# EC_Feather_Breakout_3_2.net
KiCad netlist of a schematic drawn in EAGLE
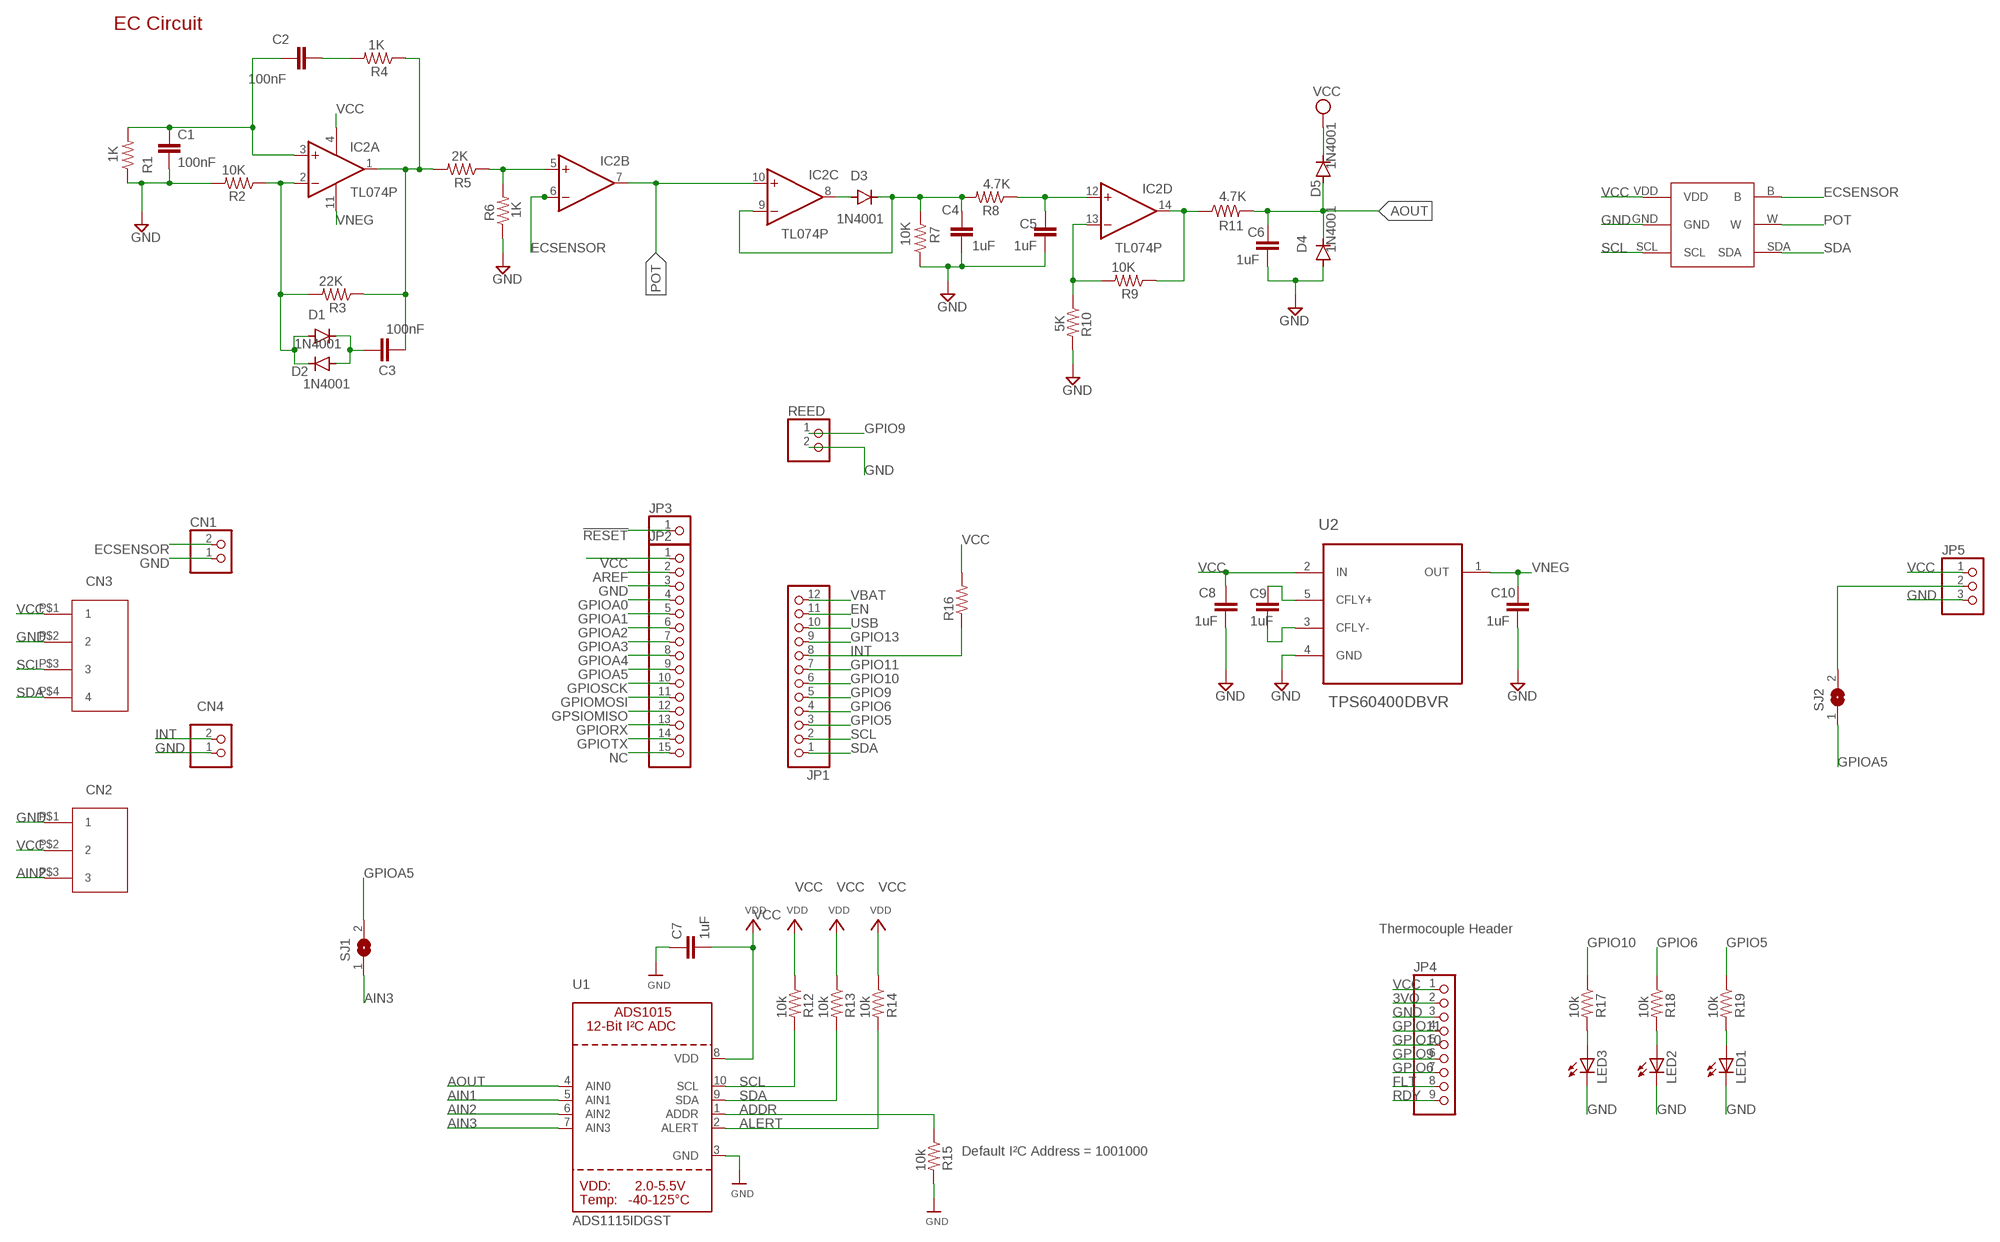
[diagram p0: schematic, sheet 1]

(export (version "E")
  (design (tool "Eeschema 10.0.6"))
  (components
    (comp (ref "C1")
      (value "100nF")
      (footprint "eagle-import:C1206")
      (libsource (lib "eagle-import") (part "C-EUC1206"))
    )
    (comp (ref "C2")
      (value "100nF")
      (footprint "eagle-import:C1206")
      (libsource (lib "eagle-import") (part "C-EUC1206"))
    )
    (comp (ref "C3")
      (value "100nF")
      (footprint "eagle-import:C1206")
      (libsource (lib "eagle-import") (part "C-EUC1206"))
    )
    (comp (ref "C4")
      (value "1uF")
      (footprint "eagle-import:C1206")
      (libsource (lib "eagle-import") (part "C-EUC1206"))
    )
    (comp (ref "C5")
      (value "1uF")
      (footprint "eagle-import:C1206")
      (libsource (lib "eagle-import") (part "C-EUC1206"))
    )
    (comp (ref "C6")
      (value "1uF")
      (footprint "eagle-import:C1206")
      (libsource (lib "eagle-import") (part "C-EUC1206"))
    )
    (comp (ref "C7")
      (value "1uF")
      (footprint "eagle-import:C1206")
      (libsource (lib "eagle-import") (part "C-EUC1206"))
    )
    (comp (ref "C8")
      (value "1uF")
      (footprint "eagle-import:C1206")
      (libsource (lib "eagle-import") (part "C-EUC1206"))
    )
    (comp (ref "C9")
      (value "1uF")
      (footprint "eagle-import:C1206")
      (libsource (lib "eagle-import") (part "C-EUC1206"))
    )
    (comp (ref "C10")
      (value "1uF")
      (footprint "eagle-import:C1206")
      (libsource (lib "eagle-import") (part "C-EUC1206"))
    )
    (comp (ref "CN1")
      (value "JST_2PIN-THM")
      (footprint "eagle-import:JST-PH-2-THM")
      (libsource (lib "eagle-import") (part "JST_2PIN-THM"))
    )
    (comp (ref "CN4")
      (value "JST_2PIN-THM")
      (footprint "eagle-import:JST-PH-2-THM")
      (libsource (lib "eagle-import") (part "JST_2PIN-THM"))
    )
    (comp (ref "D1")
      (value "1N4001")
      (footprint "eagle-import:D-5")
      (libsource (lib "eagle-import") (part "DIODE-D-5"))
    )
    (comp (ref "D2")
      (value "1N4001")
      (footprint "eagle-import:D-5")
      (libsource (lib "eagle-import") (part "DIODE-D-5"))
    )
    (comp (ref "D3")
      (value "1N4001")
      (footprint "eagle-import:D-5")
      (libsource (lib "eagle-import") (part "DIODE-D-5"))
    )
    (comp (ref "D4")
      (value "1N4001")
      (footprint "eagle-import:D-5")
      (libsource (lib "eagle-import") (part "DIODE-D-5"))
    )
    (comp (ref "D5")
      (value "1N4001")
      (footprint "eagle-import:D-5")
      (libsource (lib "eagle-import") (part "DIODE-D-5"))
    )
    (comp (ref "IC2")
      (value "TL074P")
      (footprint "eagle-import:DIL14")
      (libsource (lib "eagle-import") (part "TL074P"))
    )
    (comp (ref "JP1")
      (value "PINHD-1X12-CB")
      (footprint "eagle-import:1X12-CB")
      (libsource (lib "eagle-import") (part "PINHD-1X12-CB"))
    )
    (comp (ref "JP2")
      (value "PINHD-1X15-CB")
      (footprint "eagle-import:1X15-CB")
      (libsource (lib "eagle-import") (part "PINHD-1X15-CB"))
    )
    (comp (ref "JP3")
      (value "PINHD-1X1CB")
      (footprint "eagle-import:1X01-CLEANBIG")
      (libsource (lib "eagle-import") (part "PINHD-1X1CB"))
    )
    (comp (ref "JP4")
      (value "PINHD-1X9")
      (footprint "eagle-import:1X09")
      (libsource (lib "eagle-import") (part "PINHD-1X9"))
    )
    (comp (ref "JP5")
      (value "PINHD-1X3CB")
      (footprint "eagle-import:1X03-CLEANBIG")
      (libsource (lib "eagle-import") (part "PINHD-1X3CB"))
    )
    (comp (ref "LED1")
      (value "LEDSMT1206")
      (footprint "eagle-import:1206")
      (libsource (lib "eagle-import") (part "LEDSMT1206"))
    )
    (comp (ref "LED2")
      (value "LEDSMT1206")
      (footprint "eagle-import:1206")
      (libsource (lib "eagle-import") (part "LEDSMT1206"))
    )
    (comp (ref "LED3")
      (value "LEDSMT1206")
      (footprint "eagle-import:1206")
      (libsource (lib "eagle-import") (part "LEDSMT1206"))
    )
    (comp (ref "R1")
      (value "1K")
      (footprint "eagle-import:R1206")
      (libsource (lib "eagle-import") (part "rcl_334_R-US_R1206"))
    )
    (comp (ref "R2")
      (value "10K")
      (footprint "eagle-import:R1206")
      (libsource (lib "eagle-import") (part "rcl_334_R-US_R1206"))
    )
    (comp (ref "R3")
      (value "22K")
      (footprint "eagle-import:R1206")
      (libsource (lib "eagle-import") (part "rcl_334_R-US_R1206"))
    )
    (comp (ref "R4")
      (value "1K")
      (footprint "eagle-import:R1206")
      (libsource (lib "eagle-import") (part "rcl_334_R-US_R1206"))
    )
    (comp (ref "R5")
      (value "2K")
      (footprint "eagle-import:R1206")
      (libsource (lib "eagle-import") (part "rcl_334_R-US_R1206"))
    )
    (comp (ref "R6")
      (value "1K")
      (footprint "eagle-import:R1206")
      (libsource (lib "eagle-import") (part "rcl_334_R-US_R1206"))
    )
    (comp (ref "R7")
      (value "10K")
      (footprint "eagle-import:R1206")
      (libsource (lib "eagle-import") (part "rcl_334_R-US_R1206"))
    )
    (comp (ref "R8")
      (value "4.7K")
      (footprint "eagle-import:R1206")
      (libsource (lib "eagle-import") (part "rcl_334_R-US_R1206"))
    )
    (comp (ref "R9")
      (value "10K")
      (footprint "eagle-import:R1206")
      (libsource (lib "eagle-import") (part "rcl_334_R-US_R1206"))
    )
    (comp (ref "R10")
      (value "5K")
      (footprint "eagle-import:R1206")
      (libsource (lib "eagle-import") (part "rcl_334_R-US_R1206"))
    )
    (comp (ref "R11")
      (value "4.7K")
      (footprint "eagle-import:R1206")
      (libsource (lib "eagle-import") (part "rcl_334_R-US_R1206"))
    )
    (comp (ref "R12")
      (value "10k")
      (footprint "eagle-import:R1206")
      (libsource (lib "eagle-import") (part "rcl_334_R-US_R1206"))
    )
    (comp (ref "R13")
      (value "10k")
      (footprint "eagle-import:R1206")
      (libsource (lib "eagle-import") (part "rcl_334_R-US_R1206"))
    )
    (comp (ref "R14")
      (value "10k")
      (footprint "eagle-import:R1206")
      (libsource (lib "eagle-import") (part "rcl_334_R-US_R1206"))
    )
    (comp (ref "R15")
      (value "10k")
      (footprint "eagle-import:R1206")
      (libsource (lib "eagle-import") (part "rcl_334_R-US_R1206"))
    )
    (comp (ref "R16")
      (value "R-US_M1206")
      (footprint "eagle-import:M1206")
      (libsource (lib "eagle-import") (part "R-US_M1206"))
    )
    (comp (ref "R17")
      (value "10k")
      (footprint "eagle-import:R1206")
      (libsource (lib "eagle-import") (part "rcl_334_R-US_R1206"))
    )
    (comp (ref "R18")
      (value "10k")
      (footprint "eagle-import:R1206")
      (libsource (lib "eagle-import") (part "rcl_334_R-US_R1206"))
    )
    (comp (ref "R19")
      (value "10k")
      (footprint "eagle-import:R1206")
      (libsource (lib "eagle-import") (part "rcl_334_R-US_R1206"))
    )
    (comp (ref "REED")
      (value "PINHD-1X2")
      (footprint "eagle-import:1X02")
      (libsource (lib "eagle-import") (part "PINHD-1X2"))
    )
    (comp (ref "SJ1") (value "SJ") (footprint "eagle-import:SJ") (libsource (lib "eagle-import") (part "SJ")))
    (comp (ref "SJ2") (value "SJ") (footprint "eagle-import:SJ") (libsource (lib "eagle-import") (part "SJ")))
    (comp (ref "U$1")
      (value "AD5246")
      (footprint "eagle-import:AD5246")
      (libsource (lib "eagle-import") (part "AD5246"))
    )
    (comp (ref "U$7")
      (value "JST_4PIN_2MM")
      (footprint "eagle-import:JST_4PIN_2MM")
      (libsource (lib "eagle-import") (part "JST_4PIN_2MM"))
    )
    (comp (ref "U$9")
      (value "JST_3PIN_2MM")
      (footprint "eagle-import:JST_3PIN_2MM")
      (libsource (lib "eagle-import") (part "JST_3PIN_2MM"))
    )
    (comp (ref "U1")
      (value "ADS1115IDGST")
      (footprint "eagle-import:MSOP10")
      (libsource (lib "eagle-import") (part "ADC_ADS1015"))
    )
    (comp (ref "U2")
      (value "TPS60400DBVR")
      (footprint "eagle-import:SOT95P280X145-5N")
      (fields (field (name "MF") "Texas Instruments"))
      (libsource (lib "eagle-import") (part "TPS60400DBVR"))
    )
  )
  (nets
    (net (code "1") (name "/3VO") (class "Default")
      (node (ref "JP4") (pin "2") (pinfunction "2_2") (pintype "passive"))
    )
    (net (code "2") (name "/ADDR") (class "Default")
      (node (ref "R15") (pin "1") (pinfunction "1_1") (pintype "passive"))
      (node (ref "U1") (pin "1") (pinfunction "ADDR_1") (pintype "bidirectional"))
    )
    (net (code "3") (name "/AIN1") (class "Default")
      (node (ref "U1") (pin "5") (pinfunction "AIN1_5") (pintype "bidirectional"))
    )
    (net (code "4") (name "/AIN2") (class "Default")
      (node (ref "U$9") (pin "P$3") (pinfunction "3_P$3") (pintype "bidirectional"))
      (node (ref "U1") (pin "6") (pinfunction "AIN2_6") (pintype "bidirectional"))
    )
    (net (code "5") (name "/AIN3") (class "Default")
      (node (ref "SJ1") (pin "1") (pinfunction "1_1") (pintype "passive"))
      (node (ref "U1") (pin "7") (pinfunction "AIN3_7") (pintype "bidirectional"))
    )
    (net (code "6") (name "/ALERT") (class "Default")
      (node (ref "R14") (pin "2") (pinfunction "2_2") (pintype "passive"))
      (node (ref "U1") (pin "2") (pinfunction "ALERT_2") (pintype "bidirectional"))
    )
    (net (code "7") (name "/AREF") (class "Default")
      (node (ref "JP2") (pin "2") (pinfunction "2_2") (pintype "passive"))
    )
    (net (code "8") (name "/ECSENSOR") (class "Default")
      (node (ref "CN1") (pin "2") (pinfunction "1_2") (pintype "passive"))
      (node (ref "IC2") (pin "6") (pinfunction "-IN_6") (pintype "input"))
      (node (ref "U$1") (pin "B") (pinfunction "B_B") (pintype "bidirectional"))
    )
    (net (code "9") (name "/EN") (class "Default")
      (node (ref "JP1") (pin "11") (pinfunction "11_11") (pintype "passive"))
    )
    (net (code "10") (name "/FLT") (class "Default")
      (node (ref "JP4") (pin "8") (pinfunction "8_8") (pintype "passive"))
    )
    (net (code "11") (name "/GPIO5") (class "Default")
      (node (ref "JP1") (pin "3") (pinfunction "3_3") (pintype "passive"))
      (node (ref "R19") (pin "1") (pinfunction "1_1") (pintype "passive"))
    )
    (net (code "12") (name "/GPIO6") (class "Default")
      (node (ref "JP1") (pin "4") (pinfunction "4_4") (pintype "passive"))
      (node (ref "JP4") (pin "7") (pinfunction "7_7") (pintype "passive"))
      (node (ref "R18") (pin "1") (pinfunction "1_1") (pintype "passive"))
    )
    (net (code "13") (name "/GPIO9") (class "Default")
      (node (ref "JP1") (pin "5") (pinfunction "5_5") (pintype "passive"))
      (node (ref "JP4") (pin "6") (pinfunction "6_6") (pintype "passive"))
      (node (ref "REED") (pin "1") (pinfunction "1_1") (pintype "passive"))
    )
    (net (code "14") (name "/GPIO10") (class "Default")
      (node (ref "JP1") (pin "6") (pinfunction "6_6") (pintype "passive"))
      (node (ref "JP4") (pin "5") (pinfunction "5_5") (pintype "passive"))
      (node (ref "R17") (pin "1") (pinfunction "1_1") (pintype "passive"))
    )
    (net (code "15") (name "/GPIO11") (class "Default")
      (node (ref "JP1") (pin "7") (pinfunction "7_7") (pintype "passive"))
      (node (ref "JP4") (pin "4") (pinfunction "4_4") (pintype "passive"))
    )
    (net (code "16") (name "/GPIO13") (class "Default")
      (node (ref "JP1") (pin "9") (pinfunction "9_9") (pintype "passive"))
    )
    (net (code "17") (name "/GPIOA0") (class "Default")
      (node (ref "JP2") (pin "4") (pinfunction "4_4") (pintype "passive"))
    )
    (net (code "18") (name "/GPIOA1") (class "Default")
      (node (ref "JP2") (pin "5") (pinfunction "5_5") (pintype "passive"))
    )
    (net (code "19") (name "/GPIOA2") (class "Default")
      (node (ref "JP2") (pin "6") (pinfunction "6_6") (pintype "passive"))
    )
    (net (code "20") (name "/GPIOA3") (class "Default")
      (node (ref "JP2") (pin "7") (pinfunction "7_7") (pintype "passive"))
    )
    (net (code "21") (name "/GPIOA4") (class "Default")
      (node (ref "JP2") (pin "8") (pinfunction "8_8") (pintype "passive"))
    )
    (net (code "22") (name "/GPIOA5") (class "Default")
      (node (ref "JP2") (pin "9") (pinfunction "9_9") (pintype "passive"))
      (node (ref "SJ1") (pin "2") (pinfunction "2_2") (pintype "passive"))
      (node (ref "SJ2") (pin "1") (pinfunction "1_1") (pintype "passive"))
    )
    (net (code "23") (name "/GPIOMOSI") (class "Default")
      (node (ref "JP2") (pin "11") (pinfunction "11_11") (pintype "passive"))
    )
    (net (code "24") (name "/GPIORX") (class "Default")
      (node (ref "JP2") (pin "13") (pinfunction "13_13") (pintype "passive"))
    )
    (net (code "25") (name "/GPIOSCK") (class "Default")
      (node (ref "JP2") (pin "10") (pinfunction "10_10") (pintype "passive"))
    )
    (net (code "26") (name "/GPIOTX") (class "Default")
      (node (ref "JP2") (pin "14") (pinfunction "14_14") (pintype "passive"))
    )
    (net (code "27") (name "/GPSIOMISO") (class "Default")
      (node (ref "JP2") (pin "12") (pinfunction "12_12") (pintype "passive"))
    )
    (net (code "28") (name "/INT") (class "Default")
      (node (ref "CN4") (pin "2") (pinfunction "1_2") (pintype "passive"))
      (node (ref "JP1") (pin "8") (pinfunction "8_8") (pintype "passive"))
      (node (ref "R16") (pin "1") (pinfunction "1_1") (pintype "passive"))
    )
    (net (code "29") (name "/NC") (class "Default")
      (node (ref "JP2") (pin "15") (pinfunction "15_15") (pintype "passive"))
    )
    (net (code "30") (name "/RDY") (class "Default")
      (node (ref "JP4") (pin "9") (pinfunction "9_9") (pintype "passive"))
    )
    (net (code "31") (name "/SCL") (class "Default")
      (node (ref "JP1") (pin "2") (pinfunction "2_2") (pintype "passive"))
      (node (ref "R12") (pin "2") (pinfunction "2_2") (pintype "passive"))
      (node (ref "U$1") (pin "SCL") (pinfunction "SCL_SCL") (pintype "bidirectional"))
      (node (ref "U$7") (pin "P$3") (pinfunction "3_P$3") (pintype "bidirectional"))
      (node (ref "U1") (pin "10") (pinfunction "SCL_10") (pintype "bidirectional"))
    )
    (net (code "32") (name "/SDA") (class "Default")
      (node (ref "JP1") (pin "1") (pinfunction "1_1") (pintype "passive"))
      (node (ref "R13") (pin "2") (pinfunction "2_2") (pintype "passive"))
      (node (ref "U$1") (pin "SDA") (pinfunction "SDA_SDA") (pintype "bidirectional"))
      (node (ref "U$7") (pin "P$4") (pinfunction "4_P$4") (pintype "bidirectional"))
      (node (ref "U1") (pin "9") (pinfunction "SDA_9") (pintype "bidirectional"))
    )
    (net (code "33") (name "/USB") (class "Default")
      (node (ref "JP1") (pin "10") (pinfunction "10_10") (pintype "passive"))
    )
    (net (code "34") (name "/VBAT") (class "Default")
      (node (ref "JP1") (pin "12") (pinfunction "12_12") (pintype "passive"))
    )
    (net (code "35") (name "/VNEG") (class "Default")
      (node (ref "C10") (pin "2") (pinfunction "2_2") (pintype "passive"))
      (node (ref "IC2") (pin "11") (pinfunction "V-_11") (pintype "power_in"))
      (node (ref "U2") (pin "1") (pinfunction "OUT_1") (pintype "output"))
    )
    (net (code "36") (name "/~{RESET}") (class "Default")
      (node (ref "JP3") (pin "1") (pinfunction "1_1") (pintype "passive"))
    )
    (net (code "37") (name "AOUT") (class "Default")
      (node (ref "C6") (pin "2") (pinfunction "2_2") (pintype "passive"))
      (node (ref "D4") (pin "C") (pinfunction "C_C") (pintype "passive"))
      (node (ref "D5") (pin "A") (pinfunction "A_A") (pintype "passive"))
      (node (ref "R11") (pin "2") (pinfunction "2_2") (pintype "passive"))
      (node (ref "U1") (pin "4") (pinfunction "AIN0_4") (pintype "bidirectional"))
    )
    (net (code "38") (name "GND") (class "Default")
      (node (ref "C1") (pin "2") (pinfunction "2_2") (pintype "passive"))
      (node (ref "C10") (pin "1") (pinfunction "1_1") (pintype "passive"))
      (node (ref "C4") (pin "1") (pinfunction "1_1") (pintype "passive"))
      (node (ref "C5") (pin "1") (pinfunction "1_1") (pintype "passive"))
      (node (ref "C6") (pin "1") (pinfunction "1_1") (pintype "passive"))
      (node (ref "C7") (pin "1") (pinfunction "1_1") (pintype "passive"))
      (node (ref "C8") (pin "1") (pinfunction "1_1") (pintype "passive"))
      (node (ref "CN1") (pin "1") (pinfunction "2_1") (pintype "passive"))
      (node (ref "CN4") (pin "1") (pinfunction "2_1") (pintype "passive"))
      (node (ref "D4") (pin "A") (pinfunction "A_A") (pintype "passive"))
      (node (ref "JP2") (pin "3") (pinfunction "3_3") (pintype "passive"))
      (node (ref "JP4") (pin "3") (pinfunction "3_3") (pintype "passive"))
      (node (ref "JP5") (pin "3") (pinfunction "3_3") (pintype "passive"))
      (node (ref "LED1") (pin "C") (pinfunction "C_C") (pintype "passive"))
      (node (ref "LED2") (pin "C") (pinfunction "C_C") (pintype "passive"))
      (node (ref "LED3") (pin "C") (pinfunction "C_C") (pintype "passive"))
      (node (ref "R1") (pin "1") (pinfunction "1_1") (pintype "passive"))
      (node (ref "R10") (pin "2") (pinfunction "2_2") (pintype "passive"))
      (node (ref "R15") (pin "2") (pinfunction "2_2") (pintype "passive"))
      (node (ref "R2") (pin "2") (pinfunction "2_2") (pintype "passive"))
      (node (ref "R6") (pin "1") (pinfunction "1_1") (pintype "passive"))
      (node (ref "R7") (pin "1") (pinfunction "1_1") (pintype "passive"))
      (node (ref "REED") (pin "2") (pinfunction "2_2") (pintype "passive"))
      (node (ref "U$1") (pin "GND") (pinfunction "GND_GND") (pintype "bidirectional"))
      (node (ref "U$7") (pin "P$2") (pinfunction "2_P$2") (pintype "bidirectional"))
      (node (ref "U$9") (pin "P$1") (pinfunction "1_P$1") (pintype "bidirectional"))
      (node (ref "U1") (pin "3") (pinfunction "GND_3") (pintype "bidirectional"))
      (node (ref "U2") (pin "4") (pinfunction "GND_4") (pintype "passive"))
    )
    (net (code "39") (name "Net-(C2-Pad2)") (class "Default")
      (node (ref "C2") (pin "2") (pinfunction "2_2") (pintype "passive"))
      (node (ref "R4") (pin "2") (pinfunction "2_2") (pintype "passive"))
    )
    (net (code "40") (name "Net-(C3-Pad1)") (class "Default")
      (node (ref "C3") (pin "1") (pinfunction "1_1") (pintype "passive"))
      (node (ref "D1") (pin "C") (pinfunction "C_C") (pintype "passive"))
      (node (ref "D2") (pin "A") (pinfunction "A_A") (pintype "passive"))
    )
    (net (code "41") (name "Net-(IC2A-+IN)") (class "Default")
      (node (ref "C1") (pin "1") (pinfunction "1_1") (pintype "passive"))
      (node (ref "C2") (pin "1") (pinfunction "1_1") (pintype "passive"))
      (node (ref "IC2") (pin "3") (pinfunction "+IN_3") (pintype "input"))
      (node (ref "R1") (pin "2") (pinfunction "2_2") (pintype "passive"))
    )
    (net (code "42") (name "Net-(IC2A--IN)") (class "Default")
      (node (ref "D1") (pin "A") (pinfunction "A_A") (pintype "passive"))
      (node (ref "D2") (pin "C") (pinfunction "C_C") (pintype "passive"))
      (node (ref "IC2") (pin "2") (pinfunction "-IN_2") (pintype "input"))
      (node (ref "R2") (pin "1") (pinfunction "1_1") (pintype "passive"))
      (node (ref "R3") (pin "2") (pinfunction "2_2") (pintype "passive"))
    )
    (net (code "43") (name "Net-(IC2A-OUT)") (class "Default")
      (node (ref "C3") (pin "2") (pinfunction "2_2") (pintype "passive"))
      (node (ref "IC2") (pin "1") (pinfunction "OUT_1") (pintype "output"))
      (node (ref "R3") (pin "1") (pinfunction "1_1") (pintype "passive"))
      (node (ref "R4") (pin "1") (pinfunction "1_1") (pintype "passive"))
      (node (ref "R5") (pin "2") (pinfunction "2_2") (pintype "passive"))
    )
    (net (code "44") (name "Net-(IC2B-+IN)") (class "Default")
      (node (ref "IC2") (pin "5") (pinfunction "+IN_5") (pintype "input"))
      (node (ref "R5") (pin "1") (pinfunction "1_1") (pintype "passive"))
      (node (ref "R6") (pin "2") (pinfunction "2_2") (pintype "passive"))
    )
    (net (code "45") (name "Net-(IC2C--IN)") (class "Default")
      (node (ref "C4") (pin "2") (pinfunction "2_2") (pintype "passive"))
      (node (ref "D3") (pin "C") (pinfunction "C_C") (pintype "passive"))
      (node (ref "IC2") (pin "9") (pinfunction "-IN_9") (pintype "input"))
      (node (ref "R7") (pin "2") (pinfunction "2_2") (pintype "passive"))
      (node (ref "R8") (pin "2") (pinfunction "2_2") (pintype "passive"))
    )
    (net (code "46") (name "Net-(IC2C-OUT)") (class "Default")
      (node (ref "D3") (pin "A") (pinfunction "A_A") (pintype "passive"))
      (node (ref "IC2") (pin "8") (pinfunction "OUT_8") (pintype "output"))
    )
    (net (code "47") (name "Net-(IC2D-+IN)") (class "Default")
      (node (ref "C5") (pin "2") (pinfunction "2_2") (pintype "passive"))
      (node (ref "IC2") (pin "12") (pinfunction "+IN_12") (pintype "input"))
      (node (ref "R8") (pin "1") (pinfunction "1_1") (pintype "passive"))
    )
    (net (code "48") (name "Net-(IC2D--IN)") (class "Default")
      (node (ref "IC2") (pin "13") (pinfunction "-IN_13") (pintype "input"))
      (node (ref "R10") (pin "1") (pinfunction "1_1") (pintype "passive"))
      (node (ref "R9") (pin "2") (pinfunction "2_2") (pintype "passive"))
    )
    (net (code "49") (name "Net-(IC2D-OUT)") (class "Default")
      (node (ref "IC2") (pin "14") (pinfunction "OUT_14") (pintype "output"))
      (node (ref "R11") (pin "1") (pinfunction "1_1") (pintype "passive"))
      (node (ref "R9") (pin "1") (pinfunction "1_1") (pintype "passive"))
    )
    (net (code "50") (name "Net-(JP5-Pad2)") (class "Default")
      (node (ref "JP5") (pin "2") (pinfunction "2_2") (pintype "passive"))
      (node (ref "SJ2") (pin "2") (pinfunction "2_2") (pintype "passive"))
    )
    (net (code "51") (name "Net-(LED1-PadA)") (class "Default")
      (node (ref "LED1") (pin "A") (pinfunction "A_A") (pintype "passive"))
      (node (ref "R19") (pin "2") (pinfunction "2_2") (pintype "passive"))
    )
    (net (code "52") (name "Net-(LED2-PadA)") (class "Default")
      (node (ref "LED2") (pin "A") (pinfunction "A_A") (pintype "passive"))
      (node (ref "R18") (pin "2") (pinfunction "2_2") (pintype "passive"))
    )
    (net (code "53") (name "Net-(LED3-PadA)") (class "Default")
      (node (ref "LED3") (pin "A") (pinfunction "A_A") (pintype "passive"))
      (node (ref "R17") (pin "2") (pinfunction "2_2") (pintype "passive"))
    )
    (net (code "54") (name "Net-(U2-CFLY+)") (class "Default")
      (node (ref "C9") (pin "2") (pinfunction "2_2") (pintype "passive"))
      (node (ref "U2") (pin "5") (pinfunction "CFLY+_5") (pintype "input"))
    )
    (net (code "55") (name "Net-(U2-CFLY-)") (class "Default")
      (node (ref "C9") (pin "1") (pinfunction "1_1") (pintype "passive"))
      (node (ref "U2") (pin "3") (pinfunction "CFLY-_3") (pintype "input"))
    )
    (net (code "56") (name "POT") (class "Default")
      (node (ref "IC2") (pin "10") (pinfunction "+IN_10") (pintype "input"))
      (node (ref "IC2") (pin "7") (pinfunction "OUT_7") (pintype "output"))
      (node (ref "U$1") (pin "W") (pinfunction "W_W") (pintype "bidirectional"))
    )
    (net (code "57") (name "VCC") (class "Default")
      (node (ref "C7") (pin "2") (pinfunction "2_2") (pintype "passive"))
      (node (ref "C8") (pin "2") (pinfunction "2_2") (pintype "passive"))
      (node (ref "D5") (pin "C") (pinfunction "C_C") (pintype "passive"))
      (node (ref "IC2") (pin "4") (pinfunction "V+_4") (pintype "power_in"))
      (node (ref "JP2") (pin "1") (pinfunction "1_1") (pintype "passive"))
      (node (ref "JP4") (pin "1") (pinfunction "1_1") (pintype "passive"))
      (node (ref "JP5") (pin "1") (pinfunction "1_1") (pintype "passive"))
      (node (ref "R12") (pin "1") (pinfunction "1_1") (pintype "passive"))
      (node (ref "R13") (pin "1") (pinfunction "1_1") (pintype "passive"))
      (node (ref "R14") (pin "1") (pinfunction "1_1") (pintype "passive"))
      (node (ref "R16") (pin "2") (pinfunction "2_2") (pintype "passive"))
      (node (ref "U$1") (pin "VDD") (pinfunction "VDD_VDD") (pintype "bidirectional"))
      (node (ref "U$7") (pin "P$1") (pinfunction "1_P$1") (pintype "bidirectional"))
      (node (ref "U$9") (pin "P$2") (pinfunction "2_P$2") (pintype "bidirectional"))
      (node (ref "U1") (pin "8") (pinfunction "VDD_8") (pintype "bidirectional"))
      (node (ref "U2") (pin "2") (pinfunction "IN_2") (pintype "power_in"))
    )
  )
)
